# HardMountSensor.net
KiCad netlist of a schematic drawn in EAGLE
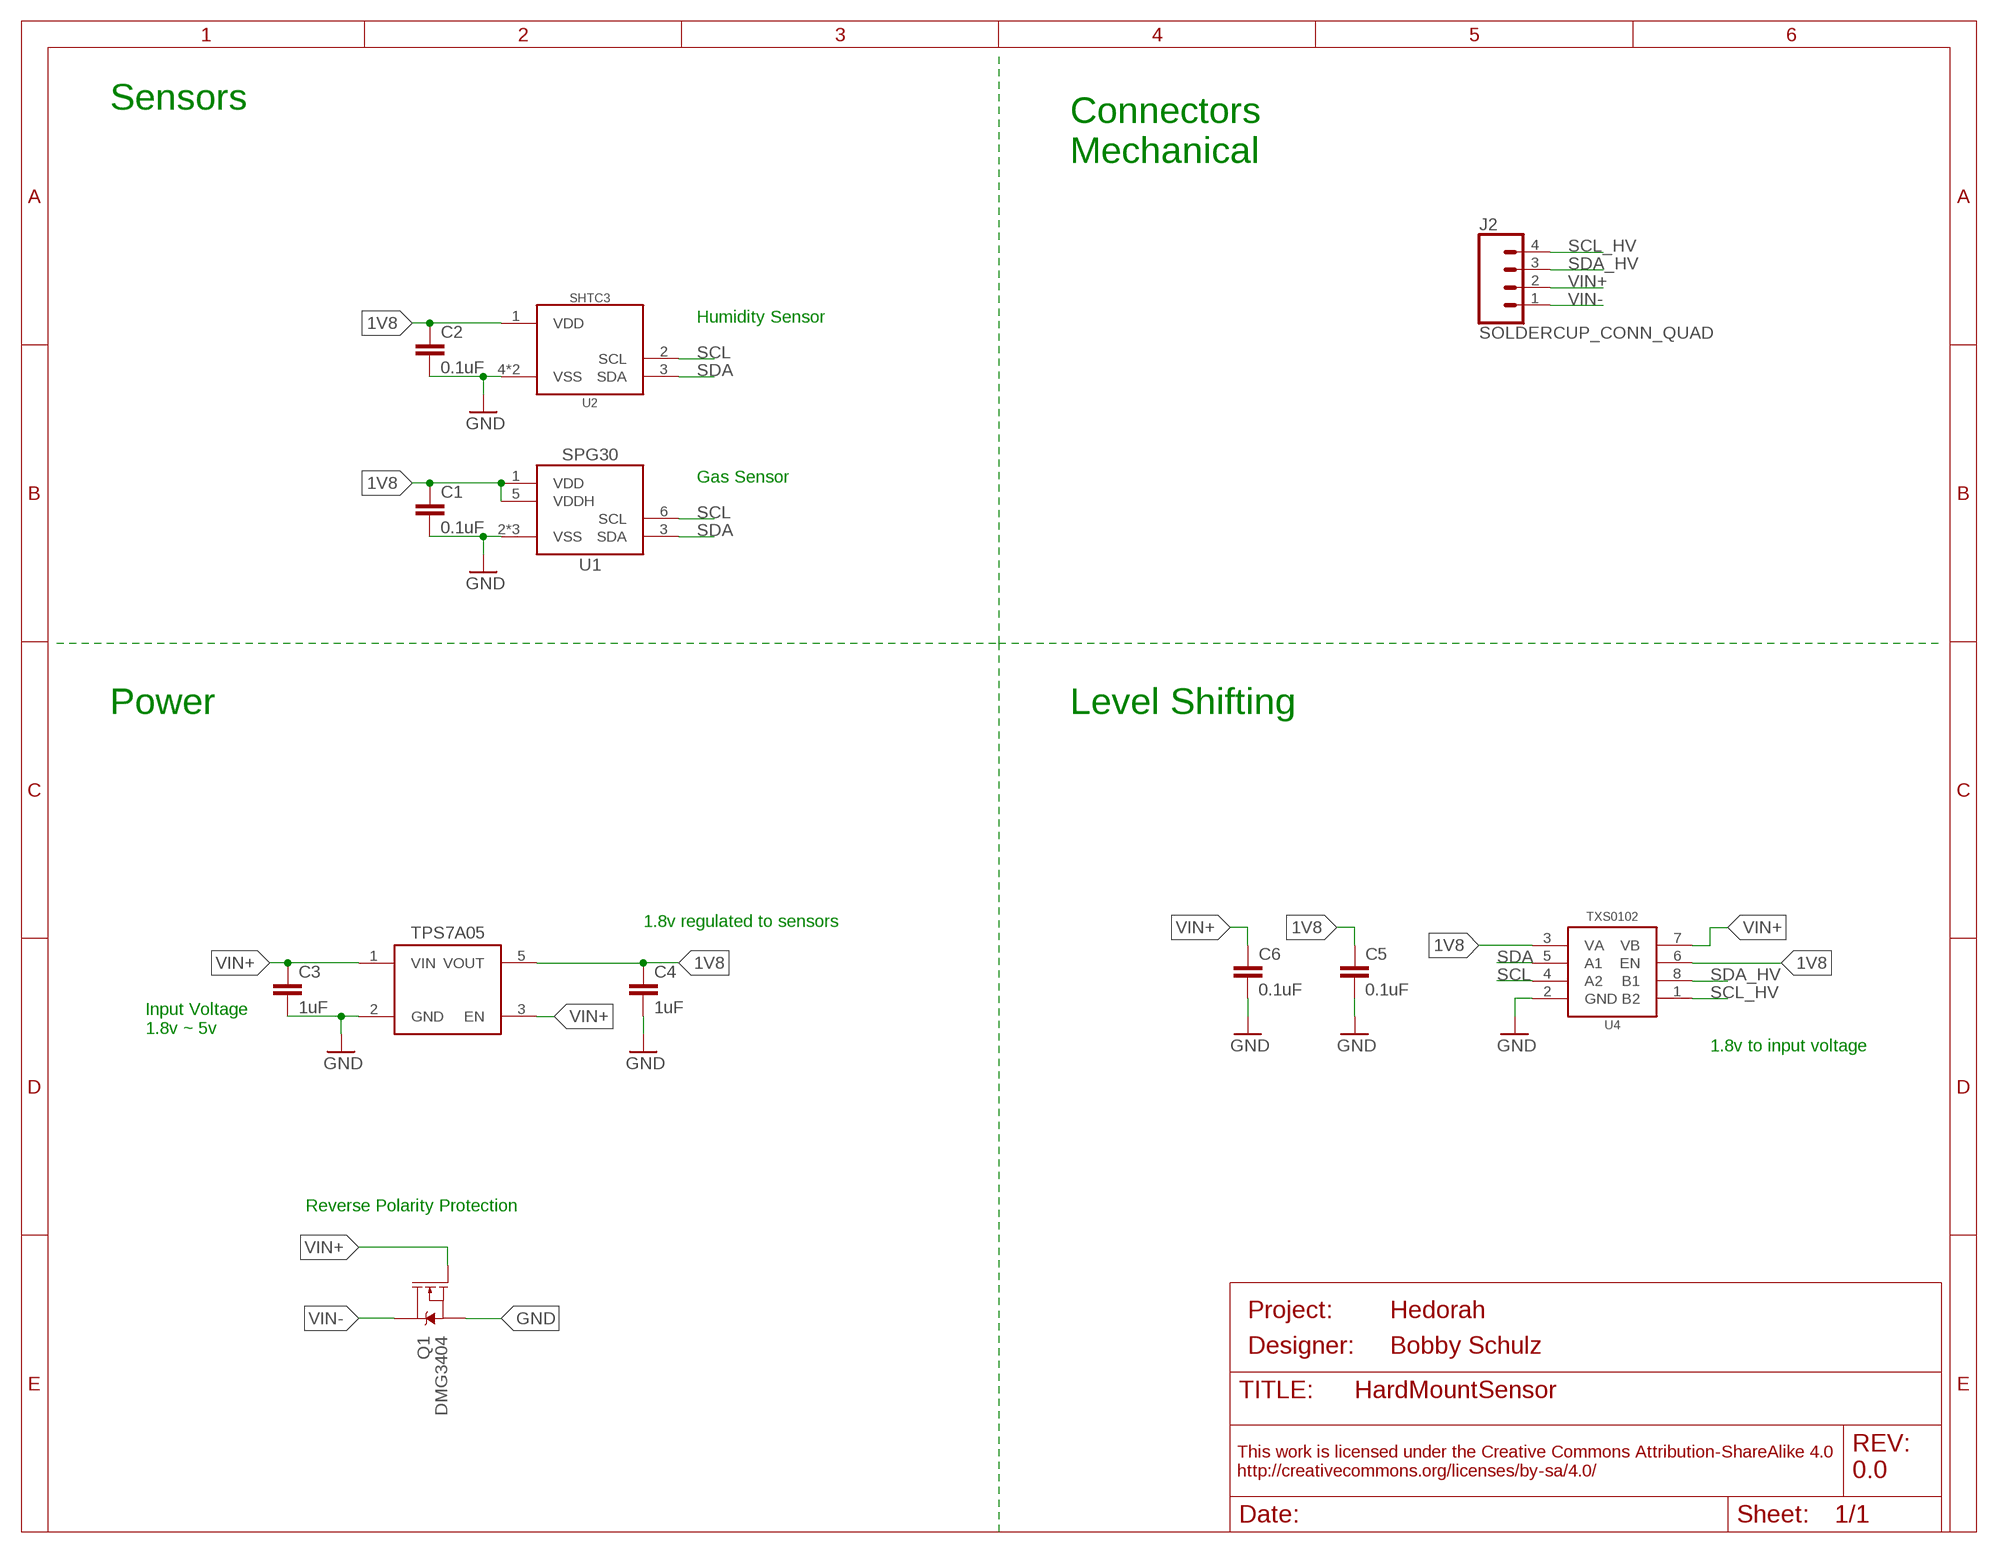
[diagram p0: schematic, sheet 1]

(export (version "E")
  (design (tool "Eeschema 10.0.6"))
  (components
    (comp (ref "C1")
      (value "0.1uF")
      (footprint "eagle-import:C0603")
      (fields (field (name "MF") "Murata") (field (name "MPN") "GCM188R71E104KA57D"))
      (libsource (lib "eagle-import") (part "C-EUC06030.1UF"))
    )
    (comp (ref "C2")
      (value "0.1uF")
      (footprint "eagle-import:C0603")
      (fields (field (name "MF") "Murata") (field (name "MPN") "GCM188R71E104KA57D"))
      (libsource (lib "eagle-import") (part "C-EUC06030.1UF"))
    )
    (comp (ref "C3")
      (value "1uF")
      (footprint "eagle-import:C0603")
      (fields (field (name "MF") "Murata") (field (name "MPN") "GRM188R61C105KA12D"))
      (libsource (lib "eagle-import") (part "C-EUC06031UF"))
    )
    (comp (ref "C4")
      (value "1uF")
      (footprint "eagle-import:C0603")
      (fields (field (name "MF") "Murata") (field (name "MPN") "GRM188R61C105KA12D"))
      (libsource (lib "eagle-import") (part "C-EUC06031UF"))
    )
    (comp (ref "C5")
      (value "0.1uF")
      (footprint "eagle-import:C0603")
      (fields (field (name "MF") "Murata") (field (name "MPN") "GCM188R71E104KA57D"))
      (libsource (lib "eagle-import") (part "C-EUC06030.1UF"))
    )
    (comp (ref "C6")
      (value "0.1uF")
      (footprint "eagle-import:C0603")
      (fields (field (name "MF") "Murata") (field (name "MPN") "GCM188R71E104KA57D"))
      (libsource (lib "eagle-import") (part "C-EUC06030.1UF"))
    )
    (comp (ref "J2")
      (value "SOLDERCUP_CONN_QUAD")
      (footprint "eagle-import:SOLDERCUP_CONN_QUAD")
      (fields (field (name "MF") "TE Connectivity") (field (name "MPN") "1838893-2"))
      (libsource (lib "eagle-import") (part "SOLDERCUP_CONN_QUAD"))
    )
    (comp (ref "Q1")
      (value "DMG3404")
      (footprint "eagle-import:SOT23-3")
      (fields (field (name "MF") "Diodes Incorporated") (field (name "MPN") "DMG3404L-7"))
      (libsource (lib "eagle-import") (part "MOSFET-NCH-DMG3404L"))
    )
    (comp (ref "U1")
      (value "SPG30")
      (footprint "eagle-import:DFN_6_2.5X2.5")
      (fields (field (name "MF") "Sensirion") (field (name "MPN") "SGP30-2.5K"))
      (libsource (lib "eagle-import") (part "SPG30"))
    )
    (comp (ref "U2")
      (value "SHTC3DFN")
      (footprint "eagle-import:DFN_4_2X2")
      (fields (field (name "DISP") "SHTC3") (field (name "MF") "Sensirion") (field (name "MPN") "SHTC3"))
      (libsource (lib "eagle-import") (part "SHTCDFN3"))
    )
    (comp (ref "U3")
      (value "TPS7A0518DBV")
      (footprint "eagle-import:SOT23-5")
      (fields
        (field (name "MF") "TI")
        (field (name "MPN") "TPS7A0518PDBVR")
        (field (name "DIGIKEY") "1649-1015-1-ND")
      )
      (libsource (lib "eagle-import") (part "TPS7A05DBV18"))
    )
    (comp (ref "U4")
      (value "TXS0102DCU")
      (footprint "eagle-import:DCU_(R-PDSO-G8)")
      (fields (field (name "MF") "TI") (field (name "MPN") "TXS0102DCUR"))
      (libsource (lib "eagle-import") (part "TXS0102DCU"))
    )
  )
  (nets
    (net (code "1") (name "/SCL") (class "Default")
      (node (ref "U1") (pin "6") (pinfunction "SCL_6") (pintype "input"))
      (node (ref "U2") (pin "2") (pinfunction "SCL_2") (pintype "input"))
      (node (ref "U4") (pin "4") (pinfunction "A2_4") (pintype "bidirectional"))
    )
    (net (code "2") (name "/SCL_HV") (class "Default")
      (node (ref "J2") (pin "4") (pinfunction "4_4") (pintype "passive"))
      (node (ref "U4") (pin "1") (pinfunction "B2_1") (pintype "bidirectional"))
    )
    (net (code "3") (name "/SDA") (class "Default")
      (node (ref "U1") (pin "3") (pinfunction "SDA_3") (pintype "bidirectional"))
      (node (ref "U2") (pin "3") (pinfunction "SDA_3") (pintype "bidirectional"))
      (node (ref "U4") (pin "5") (pinfunction "A1_5") (pintype "bidirectional"))
    )
    (net (code "4") (name "/SDA_HV") (class "Default")
      (node (ref "J2") (pin "3") (pinfunction "3_3") (pintype "passive"))
      (node (ref "U4") (pin "8") (pinfunction "B1_8") (pintype "bidirectional"))
    )
    (net (code "5") (name "1V8") (class "Default")
      (node (ref "C1") (pin "1") (pinfunction "1_1") (pintype "passive"))
      (node (ref "C2") (pin "1") (pinfunction "1_1") (pintype "passive"))
      (node (ref "C4") (pin "1") (pinfunction "1_1") (pintype "passive"))
      (node (ref "C5") (pin "1") (pinfunction "1_1") (pintype "passive"))
      (node (ref "U1") (pin "1") (pinfunction "VDD_1") (pintype "power_in"))
      (node (ref "U1") (pin "5") (pinfunction "VDDH_5") (pintype "power_in"))
      (node (ref "U2") (pin "1") (pinfunction "VDD_1") (pintype "power_in"))
      (node (ref "U3") (pin "5") (pinfunction "VOUT_5") (pintype "power_in"))
      (node (ref "U4") (pin "3") (pinfunction "VA_3") (pintype "power_in"))
      (node (ref "U4") (pin "6") (pinfunction "EN_6") (pintype "input"))
    )
    (net (code "6") (name "GND") (class "Default")
      (node (ref "C1") (pin "2") (pinfunction "2_2") (pintype "passive"))
      (node (ref "C2") (pin "2") (pinfunction "2_2") (pintype "passive"))
      (node (ref "C3") (pin "2") (pinfunction "2_2") (pintype "passive"))
      (node (ref "C4") (pin "2") (pinfunction "2_2") (pintype "passive"))
      (node (ref "C5") (pin "2") (pinfunction "2_2") (pintype "passive"))
      (node (ref "C6") (pin "2") (pinfunction "2_2") (pintype "passive"))
      (node (ref "Q1") (pin "2") (pinfunction "S_2") (pintype "bidirectional"))
      (node (ref "U1") (pin "2") (pinfunction "VSS_2") (pintype "power_in"))
      (node (ref "U1") (pin "4") (pinfunction "VSS_4") (pintype "power_in"))
      (node (ref "U1") (pin "EP") (pinfunction "VSS_EP") (pintype "power_in"))
      (node (ref "U2") (pin "4") (pinfunction "VSS_4") (pintype "power_in"))
      (node (ref "U2") (pin "EP") (pinfunction "VSS_EP") (pintype "power_in"))
      (node (ref "U3") (pin "2") (pinfunction "GND_2") (pintype "power_in"))
      (node (ref "U4") (pin "2") (pinfunction "GND_2") (pintype "power_in"))
    )
    (net (code "7") (name "VIN+") (class "Default")
      (node (ref "C3") (pin "1") (pinfunction "1_1") (pintype "passive"))
      (node (ref "C6") (pin "1") (pinfunction "1_1") (pintype "passive"))
      (node (ref "J2") (pin "2") (pinfunction "2_2") (pintype "passive"))
      (node (ref "Q1") (pin "1") (pinfunction "G_1") (pintype "bidirectional"))
      (node (ref "U3") (pin "1") (pinfunction "VIN_1") (pintype "power_in"))
      (node (ref "U3") (pin "3") (pinfunction "EN_3") (pintype "input"))
      (node (ref "U4") (pin "7") (pinfunction "VB_7") (pintype "power_in"))
    )
    (net (code "8") (name "VIN-") (class "Default")
      (node (ref "J2") (pin "1") (pinfunction "1_1") (pintype "passive"))
      (node (ref "Q1") (pin "3") (pinfunction "D_3") (pintype "bidirectional"))
    )
  )
)
